# AM-Crystal-RX-LM324.net
KiCad netlist of a schematic drawn in EAGLE
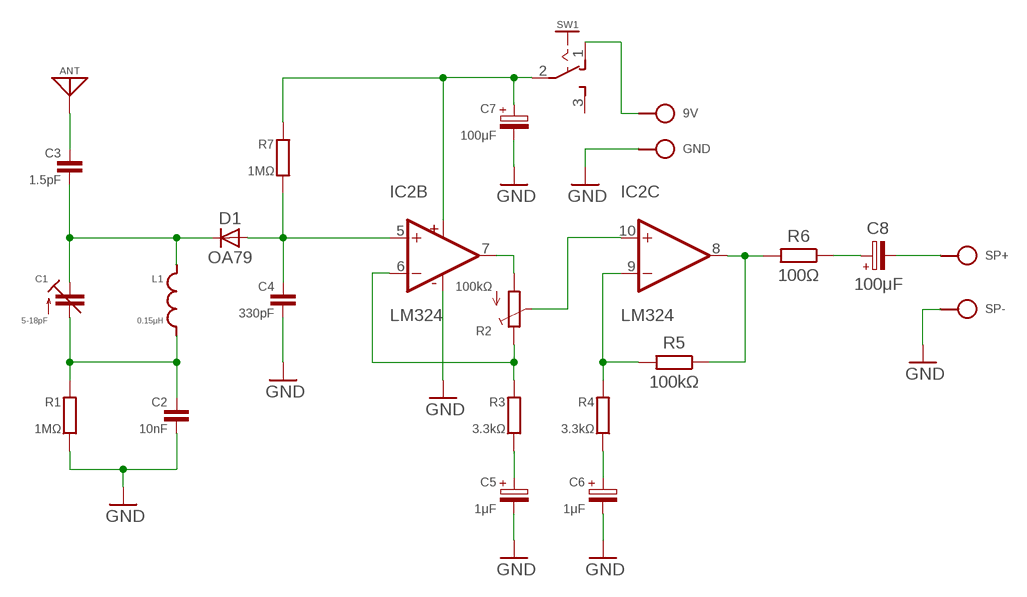
[diagram p0: schematic, sheet 1]

(export (version "E")
  (design (tool "Eeschema 10.0.6"))
  (components
    (comp (ref "9V")
      (value "BAT+")
      (footprint "eagle-import:SPAD")
      (libsource (lib "eagle-import") (part "SPAD"))
    )
    (comp (ref "ANT")
      (value "ANT")
      (footprint "eagle-import:SPAD")
      (libsource (lib "eagle-import") (part "ANT"))
    )
    (comp (ref "C1")
      (value "5-18pF")
      (footprint "eagle-import:TRIM-2222-808")
      (libsource (lib "eagle-import") (part "C-TR-PH201272222-808-2PINB"))
    )
    (comp (ref "C2")
      (value "10nF")
      (footprint "eagle-import:C050-025X075_V")
      (libsource (lib "eagle-import") (part "C050-025X075/V"))
    )
    (comp (ref "C3")
      (value "1.5pF")
      (footprint "eagle-import:C050-020X036")
      (libsource (lib "eagle-import") (part "C050-020X036"))
    )
    (comp (ref "C4")
      (value "330pF")
      (footprint "eagle-import:C050-024X044_V")
      (libsource (lib "eagle-import") (part "C050-024X044/V"))
    )
    (comp (ref "C5")
      (value "1μF")
      (footprint "eagle-import:E2.5-4_V")
      (libsource (lib "eagle-import") (part "CPOLE2,5-4/V"))
    )
    (comp (ref "C6")
      (value "1μF")
      (footprint "eagle-import:E2,5-3_V")
      (libsource (lib "eagle-import") (part "CPOLE2,5-3/V"))
    )
    (comp (ref "C7")
      (value "100μF")
      (footprint "eagle-import:E5-5_V")
      (libsource (lib "eagle-import") (part "CPOLE5-5/V"))
    )
    (comp (ref "C8")
      (value "100μF")
      (footprint "eagle-import:E2,5-5_V")
      (libsource (lib "eagle-import") (part "CPOLE2,5-5/V"))
    )
    (comp (ref "D1")
      (value "OA79")
      (footprint "eagle-import:OA79-18_V")
      (libsource (lib "eagle-import") (part "OA7918/V"))
    )
    (comp (ref "GND")
      (value "BAT-")
      (footprint "eagle-import:SPAD")
      (libsource (lib "eagle-import") (part "SPAD"))
    )
    (comp (ref "IC2")
      (value "LM324")
      (footprint "eagle-import:DIL14")
      (libsource (lib "eagle-import") (part "LM324N"))
    )
    (comp (ref "L1")
      (value "0.15μH")
      (footprint "eagle-import:L-04-5_5")
      (libsource (lib "eagle-import") (part "L-SHORT04-5/5"))
    )
    (comp (ref "R1")
      (value "1MΩ")
      (footprint "eagle-import:0202_7-V")
      (libsource (lib "eagle-import") (part "R0202/7-V"))
    )
    (comp (ref "R2")
      (value "100kΩ")
      (footprint "eagle-import:B64Y")
      (libsource (lib "eagle-import") (part "TRIM"))
    )
    (comp (ref "R3")
      (value "3.3kΩ")
      (footprint "eagle-import:0202_7")
      (libsource (lib "eagle-import") (part "R0202/7"))
    )
    (comp (ref "R4")
      (value "3.3kΩ")
      (footprint "eagle-import:0202_7-V")
      (libsource (lib "eagle-import") (part "R0202/7-V"))
    )
    (comp (ref "R5")
      (value "100kΩ")
      (footprint "eagle-import:0202_7-V")
      (libsource (lib "eagle-import") (part "R0202/7-V"))
    )
    (comp (ref "R6")
      (value "100Ω")
      (footprint "eagle-import:0202_7-V")
      (libsource (lib "eagle-import") (part "R0202/7-V"))
    )
    (comp (ref "R7")
      (value "1MΩ")
      (footprint "eagle-import:0202_7-V")
      (libsource (lib "eagle-import") (part "R0202/7-V"))
    )
    (comp (ref "SP+")
      (value "SPKR+")
      (footprint "eagle-import:SPAD")
      (libsource (lib "eagle-import") (part "SPAD"))
    )
    (comp (ref "SP-")
      (value "SPKR-")
      (footprint "eagle-import:SPAD")
      (libsource (lib "eagle-import") (part "SPAD"))
    )
    (comp (ref "SW1")
      (value "SL-SW-1P-2T-H")
      (footprint "eagle-import:SLSW-1P2T-H")
      (libsource (lib "eagle-import") (part "SL-SW-1P-2T-H"))
    )
  )
  (nets
    (net (code "1") (name "GND") (class "Default")
      (node (ref "C2") (pin "2") (pinfunction "2_2") (pintype "passive"))
      (node (ref "C4") (pin "2") (pinfunction "2_2") (pintype "passive"))
      (node (ref "C5") (pin "-") (pinfunction "-_-") (pintype "passive"))
      (node (ref "C6") (pin "-") (pinfunction "-_-") (pintype "passive"))
      (node (ref "C7") (pin "-") (pinfunction "-_-") (pintype "passive"))
      (node (ref "GND") (pin "1") (pinfunction "P$1_1") (pintype "passive"))
      (node (ref "IC2") (pin "11") (pinfunction "V-_11") (pintype "power_in"))
      (node (ref "R1") (pin "2") (pinfunction "2_2") (pintype "passive"))
      (node (ref "SP-") (pin "1") (pinfunction "P$1_1") (pintype "passive"))
    )
    (net (code "2") (name "Net-(9V-P$1)") (class "Default")
      (node (ref "9V") (pin "1") (pinfunction "P$1_1") (pintype "passive"))
      (node (ref "SW1") (pin "1") (pinfunction "O_1") (pintype "passive"))
    )
    (net (code "3") (name "Net-(ANT-Pad1)") (class "Default")
      (node (ref "ANT") (pin "1") (pinfunction "1_1") (pintype "output"))
      (node (ref "C3") (pin "1") (pinfunction "1_1") (pintype "passive"))
    )
    (net (code "4") (name "Net-(C1-A)") (class "Default")
      (node (ref "C1") (pin "3") (pinfunction "A_3") (pintype "passive"))
      (node (ref "C2") (pin "1") (pinfunction "1_1") (pintype "passive"))
      (node (ref "L1") (pin "1") (pinfunction "1_1") (pintype "passive"))
      (node (ref "R1") (pin "1") (pinfunction "1_1") (pintype "passive"))
    )
    (net (code "5") (name "Net-(C1-E)") (class "Default")
      (node (ref "C1") (pin "2") (pinfunction "E_2") (pintype "passive"))
      (node (ref "C3") (pin "2") (pinfunction "2_2") (pintype "passive"))
      (node (ref "D1") (pin "C") (pinfunction "C_C") (pintype "passive"))
      (node (ref "L1") (pin "2") (pinfunction "2_2") (pintype "passive"))
    )
    (net (code "6") (name "Net-(C5-Pad+)") (class "Default")
      (node (ref "C5") (pin "+") (pinfunction "+_+") (pintype "passive"))
      (node (ref "R3") (pin "2") (pinfunction "2_2") (pintype "passive"))
    )
    (net (code "7") (name "Net-(C6-Pad+)") (class "Default")
      (node (ref "C6") (pin "+") (pinfunction "+_+") (pintype "passive"))
      (node (ref "R4") (pin "2") (pinfunction "2_2") (pintype "passive"))
    )
    (net (code "8") (name "Net-(C8-Pad+)") (class "Default")
      (node (ref "C8") (pin "+") (pinfunction "+_+") (pintype "passive"))
      (node (ref "R6") (pin "2") (pinfunction "2_2") (pintype "passive"))
    )
    (net (code "9") (name "Net-(IC2B-+IN)") (class "Default")
      (node (ref "C4") (pin "1") (pinfunction "1_1") (pintype "passive"))
      (node (ref "D1") (pin "A") (pinfunction "A_A") (pintype "passive"))
      (node (ref "IC2") (pin "5") (pinfunction "+IN_5") (pintype "input"))
      (node (ref "R7") (pin "2") (pinfunction "2_2") (pintype "passive"))
    )
    (net (code "10") (name "Net-(IC2B--IN)") (class "Default")
      (node (ref "IC2") (pin "6") (pinfunction "-IN_6") (pintype "input"))
      (node (ref "R2") (pin "E") (pinfunction "E_E") (pintype "passive"))
      (node (ref "R3") (pin "1") (pinfunction "1_1") (pintype "passive"))
    )
    (net (code "11") (name "Net-(IC2B-OUT)") (class "Default")
      (node (ref "IC2") (pin "7") (pinfunction "OUT_7") (pintype "output"))
      (node (ref "R2") (pin "A") (pinfunction "A_A") (pintype "passive"))
    )
    (net (code "12") (name "Net-(IC2C-+IN)") (class "Default")
      (node (ref "IC2") (pin "10") (pinfunction "+IN_10") (pintype "input"))
      (node (ref "R2") (pin "S") (pinfunction "S_S") (pintype "passive"))
    )
    (net (code "13") (name "Net-(IC2C--IN)") (class "Default")
      (node (ref "IC2") (pin "9") (pinfunction "-IN_9") (pintype "input"))
      (node (ref "R4") (pin "1") (pinfunction "1_1") (pintype "passive"))
      (node (ref "R5") (pin "1") (pinfunction "1_1") (pintype "passive"))
    )
    (net (code "14") (name "Net-(IC2C-OUT)") (class "Default")
      (node (ref "IC2") (pin "8") (pinfunction "OUT_8") (pintype "output"))
      (node (ref "R5") (pin "2") (pinfunction "2_2") (pintype "passive"))
      (node (ref "R6") (pin "1") (pinfunction "1_1") (pintype "passive"))
    )
    (net (code "15") (name "Net-(IC2E-V+)") (class "Default")
      (node (ref "C7") (pin "+") (pinfunction "+_+") (pintype "passive"))
      (node (ref "IC2") (pin "4") (pinfunction "V+_4") (pintype "power_in"))
      (node (ref "R7") (pin "1") (pinfunction "1_1") (pintype "passive"))
      (node (ref "SW1") (pin "2") (pinfunction "P_2") (pintype "passive"))
    )
    (net (code "16") (name "Net-(SP+-P$1)") (class "Default")
      (node (ref "C8") (pin "-") (pinfunction "-_-") (pintype "passive"))
      (node (ref "SP+") (pin "1") (pinfunction "P$1_1") (pintype "passive"))
    )
    (net (code "17") (name "unconnected-(SW1-S-Pad3)") (class "Default")
      (node (ref "SW1") (pin "3") (pinfunction "S_3") (pintype "passive"))
    )
  )
)
